# ESP8266_Single_RGB_RevB.net
KiCad netlist of a schematic drawn in EAGLE
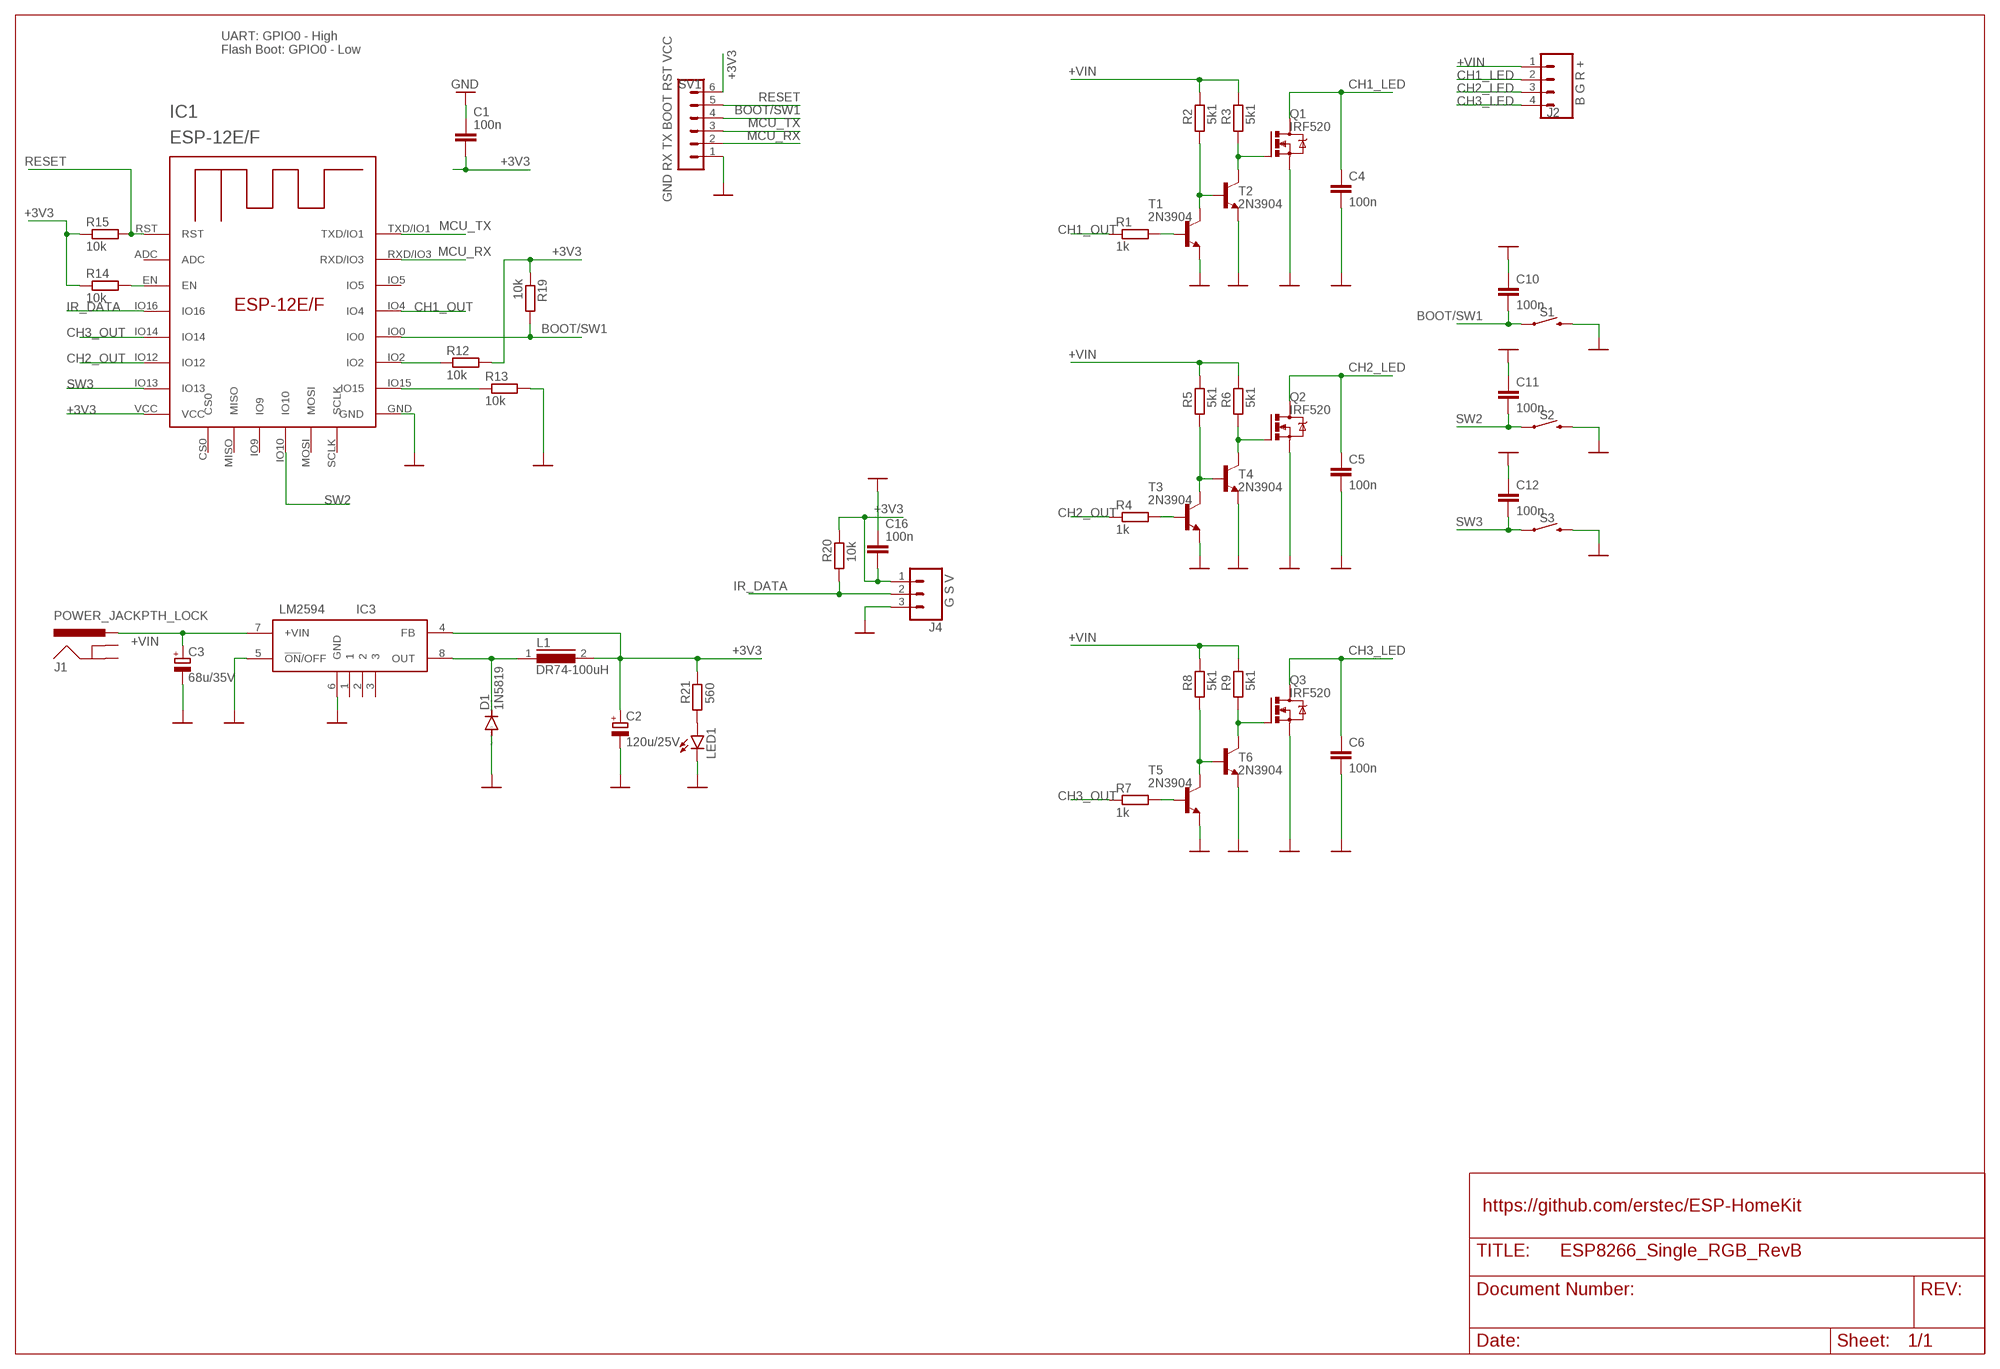
[diagram p0: schematic, sheet 1]

(export (version "E")
  (design (tool "Eeschema 10.0.6"))
  (components
    (comp (ref "C1")
      (value "100n")
      (footprint "eagle-import:C050-024X044")
      (libsource (lib "eagle-import") (part "C-EU050-024X044"))
    )
    (comp (ref "C2")
      (value "120u/25V")
      (footprint "eagle-import:E2,5-6E")
      (libsource (lib "eagle-import") (part "CPOL-EUE2,5-6E"))
    )
    (comp (ref "C3")
      (value "68u/35V")
      (footprint "eagle-import:E2,5-6")
      (libsource (lib "eagle-import") (part "CPOL-EUE2.5-6"))
    )
    (comp (ref "C4")
      (value "100n")
      (footprint "eagle-import:C050-024X044")
      (libsource (lib "eagle-import") (part "C-EU050-024X044"))
    )
    (comp (ref "C5")
      (value "100n")
      (footprint "eagle-import:C050-024X044")
      (libsource (lib "eagle-import") (part "C-EU050-024X044"))
    )
    (comp (ref "C6")
      (value "100n")
      (footprint "eagle-import:C050-024X044")
      (libsource (lib "eagle-import") (part "C-EU050-024X044"))
    )
    (comp (ref "C10")
      (value "100n")
      (footprint "eagle-import:C050-024X044")
      (libsource (lib "eagle-import") (part "C-EU050-024X044"))
    )
    (comp (ref "C11")
      (value "100n")
      (footprint "eagle-import:C050-024X044")
      (libsource (lib "eagle-import") (part "C-EU050-024X044"))
    )
    (comp (ref "C12")
      (value "100n")
      (footprint "eagle-import:C050-024X044")
      (libsource (lib "eagle-import") (part "C-EU050-024X044"))
    )
    (comp (ref "C16")
      (value "100n")
      (footprint "eagle-import:C050-024X044")
      (libsource (lib "eagle-import") (part "C-EU050-024X044"))
    )
    (comp (ref "D1")
      (value "1N5819")
      (footprint "eagle-import:DO41-7.6")
      (libsource (lib "eagle-import") (part "DIODE-DO41-7.6"))
    )
    (comp (ref "IC1")
      (value "ESP-12E/F")
      (footprint "eagle-import:ESP-12E")
      (libsource (lib "eagle-import") (part "ESP-12E/F"))
    )
    (comp (ref "IC3")
      (value "LM2594")
      (footprint "eagle-import:TSOP8")
      (fields (field (name "MF") "National Semiconductor"))
      (libsource (lib "eagle-import") (part "LM2594"))
    )
    (comp (ref "J1")
      (value "POWER_JACKPTH_LOCK")
      (footprint "eagle-import:POWER_JACK_PTH_LOCK")
      (libsource (lib "eagle-import") (part "POWER_JACKPTH_LOCK"))
    )
    (comp (ref "J2")
      (value "B G R +")
      (footprint "eagle-import:SCREWTERMINAL-3.5MM-4_LOCK")
      (libsource (lib "eagle-import") (part "CONN_04SCREW_LOCK"))
    )
    (comp (ref "J4")
      (value "G S V")
      (footprint "eagle-import:SCREWTERMINAL-3.5MM-3_LOCK.007S")
      (libsource (lib "eagle-import") (part "CONN_03SCREW_LOCK"))
    )
    (comp (ref "L1")
      (value "DR74-100uH")
      (footprint "eagle-import:DR74")
      (libsource (lib "eagle-import") (part "DR74"))
    )
    (comp (ref "LED1")
      (value "LED5MM")
      (footprint "eagle-import:LED5MM")
      (libsource (lib "eagle-import") (part "LED5MM"))
    )
    (comp (ref "Q1")
      (value "IRF520")
      (footprint "eagle-import:TO220BV")
      (libsource (lib "eagle-import") (part "IRF520"))
    )
    (comp (ref "Q2")
      (value "IRF520")
      (footprint "eagle-import:TO220BV")
      (libsource (lib "eagle-import") (part "IRF520"))
    )
    (comp (ref "Q3")
      (value "IRF520")
      (footprint "eagle-import:TO220BV")
      (libsource (lib "eagle-import") (part "IRF520"))
    )
    (comp (ref "R1")
      (value "1k")
      (footprint "eagle-import:0204_7")
      (libsource (lib "eagle-import") (part "R-EU_0204/7"))
    )
    (comp (ref "R2")
      (value "5k1")
      (footprint "eagle-import:0204_7")
      (libsource (lib "eagle-import") (part "R-EU_0204/7"))
    )
    (comp (ref "R3")
      (value "5k1")
      (footprint "eagle-import:0204_7")
      (libsource (lib "eagle-import") (part "R-EU_0204/7"))
    )
    (comp (ref "R4")
      (value "1k")
      (footprint "eagle-import:0204_7")
      (libsource (lib "eagle-import") (part "R-EU_0204/7"))
    )
    (comp (ref "R5")
      (value "5k1")
      (footprint "eagle-import:0204_7")
      (libsource (lib "eagle-import") (part "R-EU_0204/7"))
    )
    (comp (ref "R6")
      (value "5k1")
      (footprint "eagle-import:0204_7")
      (libsource (lib "eagle-import") (part "R-EU_0204/7"))
    )
    (comp (ref "R7")
      (value "1k")
      (footprint "eagle-import:0204_7")
      (libsource (lib "eagle-import") (part "R-EU_0204/7"))
    )
    (comp (ref "R8")
      (value "5k1")
      (footprint "eagle-import:0204_7")
      (libsource (lib "eagle-import") (part "R-EU_0204/7"))
    )
    (comp (ref "R9")
      (value "5k1")
      (footprint "eagle-import:0204_7")
      (libsource (lib "eagle-import") (part "R-EU_0204/7"))
    )
    (comp (ref "R12")
      (value "10k")
      (footprint "eagle-import:0204_7")
      (libsource (lib "eagle-import") (part "R-EU_0204/7"))
    )
    (comp (ref "R13")
      (value "10k")
      (footprint "eagle-import:0204_7")
      (libsource (lib "eagle-import") (part "R-EU_0204/7"))
    )
    (comp (ref "R14")
      (value "10k")
      (footprint "eagle-import:0204_7")
      (libsource (lib "eagle-import") (part "R-EU_0204/7"))
    )
    (comp (ref "R15")
      (value "10k")
      (footprint "eagle-import:0204_7")
      (libsource (lib "eagle-import") (part "R-EU_0204/7"))
    )
    (comp (ref "R19")
      (value "10k")
      (footprint "eagle-import:0204_7")
      (libsource (lib "eagle-import") (part "R-EU_0204/7"))
    )
    (comp (ref "R20")
      (value "10k")
      (footprint "eagle-import:0204_7")
      (libsource (lib "eagle-import") (part "R-EU_0204/7"))
    )
    (comp (ref "R21")
      (value "560")
      (footprint "eagle-import:0204_7")
      (libsource (lib "eagle-import") (part "R-EU_0204/7"))
    )
    (comp (ref "S1")
      (value "MOMENTARY-SWITCH-SPST-PTH-6.0MM")
      (footprint "eagle-import:TACTILE_SWITCH_PTH_6.0MM")
      (libsource (lib "eagle-import") (part "MOMENTARY-SWITCH-SPST-PTH-6.0MM"))
    )
    (comp (ref "S2")
      (value "MOMENTARY-SWITCH-SPST-PTH-6.0MM")
      (footprint "eagle-import:TACTILE_SWITCH_PTH_6.0MM")
      (libsource (lib "eagle-import") (part "MOMENTARY-SWITCH-SPST-PTH-6.0MM"))
    )
    (comp (ref "S3")
      (value "MOMENTARY-SWITCH-SPST-PTH-6.0MM")
      (footprint "eagle-import:TACTILE_SWITCH_PTH_6.0MM")
      (libsource (lib "eagle-import") (part "MOMENTARY-SWITCH-SPST-PTH-6.0MM"))
    )
    (comp (ref "SV1")
      (value "GND RX TX BOOT RST VCC")
      (footprint "eagle-import:MA06-1")
      (libsource (lib "eagle-import") (part "MA06-1"))
    )
    (comp (ref "T1")
      (value "2N3904")
      (footprint "eagle-import:TO92-EBC")
      (libsource (lib "eagle-import") (part "-NPN-TO92-EBC2N3904"))
    )
    (comp (ref "T2")
      (value "2N3904")
      (footprint "eagle-import:TO92-EBC")
      (libsource (lib "eagle-import") (part "-NPN-TO92-EBC2N3904"))
    )
    (comp (ref "T3")
      (value "2N3904")
      (footprint "eagle-import:TO92-EBC")
      (libsource (lib "eagle-import") (part "-NPN-TO92-EBC2N3904"))
    )
    (comp (ref "T4")
      (value "2N3904")
      (footprint "eagle-import:TO92-EBC")
      (libsource (lib "eagle-import") (part "-NPN-TO92-EBC2N3904"))
    )
    (comp (ref "T5")
      (value "2N3904")
      (footprint "eagle-import:TO92-EBC")
      (libsource (lib "eagle-import") (part "-NPN-TO92-EBC2N3904"))
    )
    (comp (ref "T6")
      (value "2N3904")
      (footprint "eagle-import:TO92-EBC")
      (libsource (lib "eagle-import") (part "-NPN-TO92-EBC2N3904"))
    )
  )
  (nets
    (net (code "1") (name "/+3V3") (class "Default")
      (node (ref "C1") (pin "2") (pinfunction "2_2") (pintype "passive"))
      (node (ref "C16") (pin "2") (pinfunction "2_2") (pintype "passive"))
      (node (ref "C2") (pin "+") (pinfunction "+_+") (pintype "passive"))
      (node (ref "IC1") (pin "VCC") (pinfunction "VCC_VCC") (pintype "power_in"))
      (node (ref "IC3") (pin "4") (pinfunction "FB_4") (pintype "bidirectional"))
      (node (ref "J4") (pin "1") (pinfunction "1_1") (pintype "passive"))
      (node (ref "L1") (pin "2") (pinfunction "2_2") (pintype "passive"))
      (node (ref "R12") (pin "2") (pinfunction "2_2") (pintype "passive"))
      (node (ref "R14") (pin "1") (pinfunction "1_1") (pintype "passive"))
      (node (ref "R15") (pin "1") (pinfunction "1_1") (pintype "passive"))
      (node (ref "R19") (pin "1") (pinfunction "1_1") (pintype "passive"))
      (node (ref "R20") (pin "2") (pinfunction "2_2") (pintype "passive"))
      (node (ref "R21") (pin "2") (pinfunction "2_2") (pintype "passive"))
      (node (ref "SV1") (pin "6") (pinfunction "6_6") (pintype "passive"))
    )
    (net (code "2") (name "/+VIN") (class "Default")
      (node (ref "C3") (pin "+") (pinfunction "+_+") (pintype "passive"))
      (node (ref "IC3") (pin "7") (pinfunction "+VIN_7") (pintype "bidirectional"))
      (node (ref "J1") (pin "PWR") (pinfunction "PWR_PWR") (pintype "bidirectional"))
      (node (ref "J2") (pin "1") (pinfunction "1_1") (pintype "passive"))
      (node (ref "R2") (pin "2") (pinfunction "2_2") (pintype "passive"))
      (node (ref "R3") (pin "2") (pinfunction "2_2") (pintype "passive"))
      (node (ref "R5") (pin "2") (pinfunction "2_2") (pintype "passive"))
      (node (ref "R6") (pin "2") (pinfunction "2_2") (pintype "passive"))
      (node (ref "R8") (pin "2") (pinfunction "2_2") (pintype "passive"))
      (node (ref "R9") (pin "2") (pinfunction "2_2") (pintype "passive"))
    )
    (net (code "3") (name "/BOOT{slash}SW1") (class "Default")
      (node (ref "C10") (pin "2") (pinfunction "2_2") (pintype "passive"))
      (node (ref "IC1") (pin "IO0") (pinfunction "IO0_IO0") (pintype "bidirectional"))
      (node (ref "R19") (pin "2") (pinfunction "2_2") (pintype "passive"))
      (node (ref "S1") (pin "1") (pinfunction "1_1") (pintype "passive"))
      (node (ref "SV1") (pin "4") (pinfunction "4_4") (pintype "passive"))
    )
    (net (code "4") (name "/CH1_LED") (class "Default")
      (node (ref "C4") (pin "1") (pinfunction "1_1") (pintype "passive"))
      (node (ref "J2") (pin "2") (pinfunction "2_2") (pintype "passive"))
      (node (ref "Q1") (pin "D") (pinfunction "D_D") (pintype "passive"))
    )
    (net (code "5") (name "/CH1_OUT") (class "Default")
      (node (ref "IC1") (pin "IO4") (pinfunction "IO4_IO4") (pintype "bidirectional"))
      (node (ref "R1") (pin "1") (pinfunction "1_1") (pintype "passive"))
    )
    (net (code "6") (name "/CH2_LED") (class "Default")
      (node (ref "C5") (pin "1") (pinfunction "1_1") (pintype "passive"))
      (node (ref "J2") (pin "3") (pinfunction "3_3") (pintype "passive"))
      (node (ref "Q2") (pin "D") (pinfunction "D_D") (pintype "passive"))
    )
    (net (code "7") (name "/CH2_OUT") (class "Default")
      (node (ref "IC1") (pin "IO12") (pinfunction "IO12_IO12") (pintype "bidirectional"))
      (node (ref "R4") (pin "1") (pinfunction "1_1") (pintype "passive"))
    )
    (net (code "8") (name "/CH3_LED") (class "Default")
      (node (ref "C6") (pin "1") (pinfunction "1_1") (pintype "passive"))
      (node (ref "J2") (pin "4") (pinfunction "4_4") (pintype "passive"))
      (node (ref "Q3") (pin "D") (pinfunction "D_D") (pintype "passive"))
    )
    (net (code "9") (name "/CH3_OUT") (class "Default")
      (node (ref "IC1") (pin "IO14") (pinfunction "IO14_IO14") (pintype "bidirectional"))
      (node (ref "R7") (pin "1") (pinfunction "1_1") (pintype "passive"))
    )
    (net (code "10") (name "/IR_DATA") (class "Default")
      (node (ref "IC1") (pin "IO16") (pinfunction "IO16_IO16") (pintype "bidirectional"))
      (node (ref "J4") (pin "2") (pinfunction "2_2") (pintype "passive"))
      (node (ref "R20") (pin "1") (pinfunction "1_1") (pintype "passive"))
    )
    (net (code "11") (name "/MCU_RX") (class "Default")
      (node (ref "IC1") (pin "RXD/IO3") (pinfunction "RXD/IO3_RXD/IO3") (pintype "bidirectional"))
      (node (ref "SV1") (pin "2") (pinfunction "2_2") (pintype "passive"))
    )
    (net (code "12") (name "/MCU_TX") (class "Default")
      (node (ref "IC1") (pin "TXD/IO1") (pinfunction "TXD/IO1_TXD/IO1") (pintype "bidirectional"))
      (node (ref "SV1") (pin "3") (pinfunction "3_3") (pintype "passive"))
    )
    (net (code "13") (name "/RESET") (class "Default")
      (node (ref "IC1") (pin "RST") (pinfunction "RST_RST") (pintype "input"))
      (node (ref "R15") (pin "2") (pinfunction "2_2") (pintype "passive"))
      (node (ref "SV1") (pin "5") (pinfunction "5_5") (pintype "passive"))
    )
    (net (code "14") (name "/SW2") (class "Default")
      (node (ref "C11") (pin "2") (pinfunction "2_2") (pintype "passive"))
      (node (ref "IC1") (pin "IO10") (pinfunction "IO10_IO10") (pintype "bidirectional"))
      (node (ref "S2") (pin "1") (pinfunction "1_1") (pintype "passive"))
    )
    (net (code "15") (name "/SW3") (class "Default")
      (node (ref "C12") (pin "2") (pinfunction "2_2") (pintype "passive"))
      (node (ref "IC1") (pin "IO13") (pinfunction "IO13_IO13") (pintype "bidirectional"))
      (node (ref "S3") (pin "1") (pinfunction "1_1") (pintype "passive"))
    )
    (net (code "16") (name "GND") (class "Default")
      (node (ref "C1") (pin "1") (pinfunction "1_1") (pintype "passive"))
      (node (ref "C10") (pin "1") (pinfunction "1_1") (pintype "passive"))
      (node (ref "C11") (pin "1") (pinfunction "1_1") (pintype "passive"))
      (node (ref "C12") (pin "1") (pinfunction "1_1") (pintype "passive"))
      (node (ref "C16") (pin "1") (pinfunction "1_1") (pintype "passive"))
      (node (ref "C2") (pin "-") (pinfunction "-_-") (pintype "passive"))
      (node (ref "C3") (pin "-") (pinfunction "-_-") (pintype "passive"))
      (node (ref "C4") (pin "2") (pinfunction "2_2") (pintype "passive"))
      (node (ref "C5") (pin "2") (pinfunction "2_2") (pintype "passive"))
      (node (ref "C6") (pin "2") (pinfunction "2_2") (pintype "passive"))
      (node (ref "D1") (pin "A") (pinfunction "A_A") (pintype "passive"))
      (node (ref "IC1") (pin "GND") (pinfunction "GND_GND") (pintype "power_in"))
      (node (ref "IC3") (pin "5") (pinfunction "~{ON}/OFF_5") (pintype "bidirectional"))
      (node (ref "IC3") (pin "6") (pinfunction "GND_6") (pintype "bidirectional"))
      (node (ref "J4") (pin "3") (pinfunction "3_3") (pintype "passive"))
      (node (ref "LED1") (pin "K") (pinfunction "C_K") (pintype "passive"))
      (node (ref "Q1") (pin "S") (pinfunction "S_S") (pintype "passive"))
      (node (ref "Q2") (pin "S") (pinfunction "S_S") (pintype "passive"))
      (node (ref "Q3") (pin "S") (pinfunction "S_S") (pintype "passive"))
      (node (ref "R13") (pin "2") (pinfunction "2_2") (pintype "passive"))
      (node (ref "S1") (pin "3") (pinfunction "2_3") (pintype "passive"))
      (node (ref "S2") (pin "3") (pinfunction "2_3") (pintype "passive"))
      (node (ref "S3") (pin "3") (pinfunction "2_3") (pintype "passive"))
      (node (ref "SV1") (pin "1") (pinfunction "1_1") (pintype "passive"))
      (node (ref "T1") (pin "E") (pinfunction "E_E") (pintype "passive"))
      (node (ref "T2") (pin "E") (pinfunction "E_E") (pintype "passive"))
      (node (ref "T3") (pin "E") (pinfunction "E_E") (pintype "passive"))
      (node (ref "T4") (pin "E") (pinfunction "E_E") (pintype "passive"))
      (node (ref "T5") (pin "E") (pinfunction "E_E") (pintype "passive"))
      (node (ref "T6") (pin "E") (pinfunction "E_E") (pintype "passive"))
    )
    (net (code "17") (name "Net-(IC1-PadEN)") (class "Default")
      (node (ref "IC1") (pin "EN") (pinfunction "EN_EN") (pintype "bidirectional"))
      (node (ref "R14") (pin "2") (pinfunction "2_2") (pintype "passive"))
    )
    (net (code "18") (name "Net-(IC1-PadIO2)") (class "Default")
      (node (ref "IC1") (pin "IO2") (pinfunction "IO2_IO2") (pintype "bidirectional"))
      (node (ref "R12") (pin "1") (pinfunction "1_1") (pintype "passive"))
    )
    (net (code "19") (name "Net-(IC1-PadIO15)") (class "Default")
      (node (ref "IC1") (pin "IO15") (pinfunction "IO15_IO15") (pintype "bidirectional"))
      (node (ref "R13") (pin "1") (pinfunction "1_1") (pintype "passive"))
    )
    (net (code "20") (name "Net-(IC3-OUT)") (class "Default")
      (node (ref "D1") (pin "C") (pinfunction "C_C") (pintype "passive"))
      (node (ref "IC3") (pin "8") (pinfunction "OUT_8") (pintype "bidirectional"))
      (node (ref "L1") (pin "1") (pinfunction "1_1") (pintype "passive"))
    )
    (net (code "21") (name "Net-(LED1-PadA)") (class "Default")
      (node (ref "LED1") (pin "A") (pinfunction "A_A") (pintype "passive"))
      (node (ref "R21") (pin "1") (pinfunction "1_1") (pintype "passive"))
    )
    (net (code "22") (name "Net-(Q1-PadG)") (class "Default")
      (node (ref "Q1") (pin "G") (pinfunction "G_G") (pintype "passive"))
      (node (ref "R3") (pin "1") (pinfunction "1_1") (pintype "passive"))
      (node (ref "T2") (pin "C") (pinfunction "C_C") (pintype "passive"))
    )
    (net (code "23") (name "Net-(Q2-PadG)") (class "Default")
      (node (ref "Q2") (pin "G") (pinfunction "G_G") (pintype "passive"))
      (node (ref "R6") (pin "1") (pinfunction "1_1") (pintype "passive"))
      (node (ref "T4") (pin "C") (pinfunction "C_C") (pintype "passive"))
    )
    (net (code "24") (name "Net-(Q3-PadG)") (class "Default")
      (node (ref "Q3") (pin "G") (pinfunction "G_G") (pintype "passive"))
      (node (ref "R9") (pin "1") (pinfunction "1_1") (pintype "passive"))
      (node (ref "T6") (pin "C") (pinfunction "C_C") (pintype "passive"))
    )
    (net (code "25") (name "Net-(R1-Pad2)") (class "Default")
      (node (ref "R1") (pin "2") (pinfunction "2_2") (pintype "passive"))
      (node (ref "T1") (pin "B") (pinfunction "B_B") (pintype "passive"))
    )
    (net (code "26") (name "Net-(R2-Pad1)") (class "Default")
      (node (ref "R2") (pin "1") (pinfunction "1_1") (pintype "passive"))
      (node (ref "T1") (pin "C") (pinfunction "C_C") (pintype "passive"))
      (node (ref "T2") (pin "B") (pinfunction "B_B") (pintype "passive"))
    )
    (net (code "27") (name "Net-(R4-Pad2)") (class "Default")
      (node (ref "R4") (pin "2") (pinfunction "2_2") (pintype "passive"))
      (node (ref "T3") (pin "B") (pinfunction "B_B") (pintype "passive"))
    )
    (net (code "28") (name "Net-(R5-Pad1)") (class "Default")
      (node (ref "R5") (pin "1") (pinfunction "1_1") (pintype "passive"))
      (node (ref "T3") (pin "C") (pinfunction "C_C") (pintype "passive"))
      (node (ref "T4") (pin "B") (pinfunction "B_B") (pintype "passive"))
    )
    (net (code "29") (name "Net-(R7-Pad2)") (class "Default")
      (node (ref "R7") (pin "2") (pinfunction "2_2") (pintype "passive"))
      (node (ref "T5") (pin "B") (pinfunction "B_B") (pintype "passive"))
    )
    (net (code "30") (name "Net-(R8-Pad1)") (class "Default")
      (node (ref "R8") (pin "1") (pinfunction "1_1") (pintype "passive"))
      (node (ref "T5") (pin "C") (pinfunction "C_C") (pintype "passive"))
      (node (ref "T6") (pin "B") (pinfunction "B_B") (pintype "passive"))
    )
    (net (code "31") (name "unconnected-(IC1-PadADC)") (class "Default")
      (node (ref "IC1") (pin "ADC") (pinfunction "ADC_ADC") (pintype "bidirectional"))
    )
    (net (code "32") (name "unconnected-(IC1-PadCS0)") (class "Default")
      (node (ref "IC1") (pin "CS0") (pinfunction "CS0_CS0") (pintype "bidirectional"))
    )
    (net (code "33") (name "unconnected-(IC1-PadIO5)") (class "Default")
      (node (ref "IC1") (pin "IO5") (pinfunction "IO5_IO5") (pintype "bidirectional"))
    )
    (net (code "34") (name "unconnected-(IC1-PadIO9)") (class "Default")
      (node (ref "IC1") (pin "IO9") (pinfunction "IO9_IO9") (pintype "bidirectional"))
    )
    (net (code "35") (name "unconnected-(IC1-PadMISO)") (class "Default")
      (node (ref "IC1") (pin "MISO") (pinfunction "MISO_MISO") (pintype "bidirectional"))
    )
    (net (code "36") (name "unconnected-(IC1-PadMOSI)") (class "Default")
      (node (ref "IC1") (pin "MOSI") (pinfunction "MOSI_MOSI") (pintype "bidirectional"))
    )
    (net (code "37") (name "unconnected-(IC1-PadSCLK)") (class "Default")
      (node (ref "IC1") (pin "SCLK") (pinfunction "SCLK_SCLK") (pintype "bidirectional"))
    )
    (net (code "38") (name "unconnected-(IC3-Pad1)") (class "Default")
      (node (ref "IC3") (pin "1") (pinfunction "1_1") (pintype "bidirectional"))
    )
    (net (code "39") (name "unconnected-(IC3-Pad2)") (class "Default")
      (node (ref "IC3") (pin "2") (pinfunction "2_2") (pintype "bidirectional"))
    )
    (net (code "40") (name "unconnected-(IC3-Pad3)") (class "Default")
      (node (ref "IC3") (pin "3") (pinfunction "3_3") (pintype "bidirectional"))
    )
    (net (code "41") (name "unconnected-(J1-PadGND)") (class "Default")
      (node (ref "J1") (pin "GND") (pinfunction "GND_GND") (pintype "bidirectional"))
    )
    (net (code "42") (name "unconnected-(J1-PadGNDBREAK)") (class "Default")
      (node (ref "J1") (pin "GNDBREAK") (pinfunction "GNDBREAK_GNDBREAK") (pintype "bidirectional"))
    )
  )
)
